# ESP8266_WS.net
KiCad netlist of a schematic drawn in EasyEDA
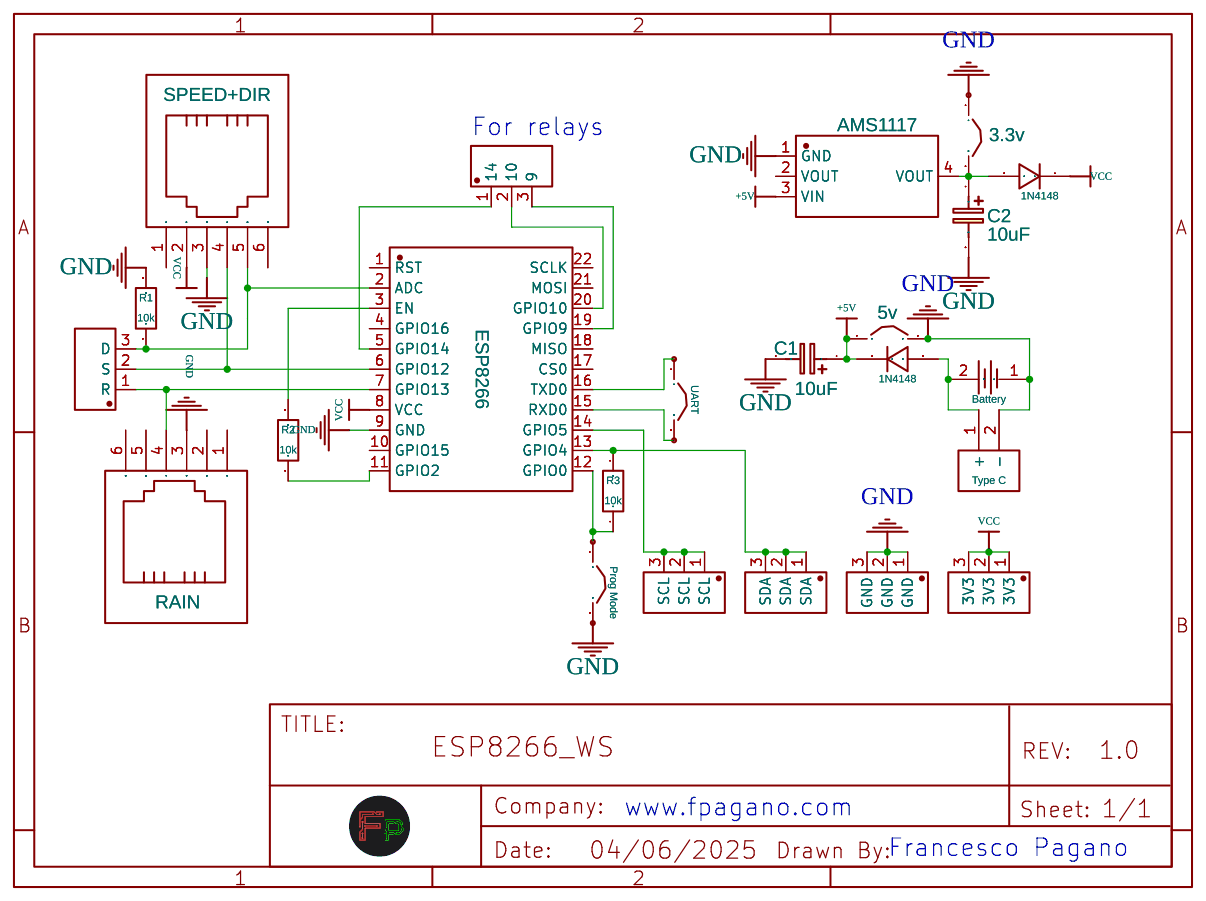
[diagram p0: schematic sheet]

(export (version "E")
  (design (tool "Eeschema 10.0.6"))
  (components
    (comp (ref "3V3") (value "3V3") (libsource (lib "") (part "HEADER FEMALE 2.54 1X3_5")))
    (comp (ref "AMS1117")
      (value "AMS1117")
      (fields (field (name "Manufacturer Part") "AMS1117-3.3") (field (name "Manufacturer") "AMS"))
      (libsource (lib "") (part "AMS1117-3.3"))
    )
    (comp (ref "BATTERY")
      (value "Battery")
      (fields
        (field (name "Manufacturer Part") "BH-18650-B6AA002")
        (field (name "Manufacturer") "MYOUNG(美阳)")
      )
      (libsource (lib "") (part "BH-18650-B6AA002"))
    )
    (comp (ref "C1") (value "10uF") (libsource (lib "") (part "CE_TH_D4.0×F1.5_EU_1")))
    (comp (ref "C2") (value "10uF") (libsource (lib "") (part "CE_TH_D4.0×F1.5_EU")))
    (comp (ref "D1")
      (value "1N4148")
      (fields (field (name "Manufacturer") "STMicroelectronics"))
      (libsource (lib "") (part "1N4148_1"))
    )
    (comp (ref "D2")
      (value "1N4148")
      (fields (field (name "Manufacturer") "STMicroelectronics"))
      (libsource (lib "") (part "1N4148"))
    )
    (comp (ref "ESP8266") (value "ESP8266") (libsource (lib "") (part "ESP8266")))
    (comp (ref "GND") (value "GND") (libsource (lib "") (part "HEADER FEMALE 2.54 1X3_3")))
    (comp (ref "GPIO") (value "GPIO") (libsource (lib "") (part "HEADER FEMALE 2.54 1X3_4")))
    (comp (ref "J-3V3")
      (value "3.3v")
      (fields (field (name "Manufacturer Part") "NONE"))
      (libsource (lib "") (part "JUMPERTHRUHOLE_2"))
    )
    (comp (ref "J-5V")
      (value "5v")
      (fields (field (name "Manufacturer Part") "NONE"))
      (libsource (lib "") (part "JUMPERTHRUHOLE"))
    )
    (comp (ref "OUT") (value "OUT") (libsource (lib "") (part "HEADER FEMALE 2.54 1X3_2")))
    (comp (ref "PROG-MODE")
      (value "Prog Mode")
      (fields (field (name "Manufacturer Part") "NONE"))
      (libsource (lib "") (part "JUMPERTHRUHOLE_3"))
    )
    (comp (ref "R1") (value "10k") (libsource (lib "") (part "R_AXIAL-0.3_EU")))
    (comp (ref "R2") (value "10k") (libsource (lib "") (part "R_AXIAL-0.3_EU")))
    (comp (ref "R3") (value "10k") (libsource (lib "") (part "R_AXIAL-0.3_EU")))
    (comp (ref "RAIN")
      (value "RAIN")
      (fields (field (name "Manufacturer Part") "331-6421") (field (name "Manufacturer") "RS PRO"))
      (libsource (lib "") (part "ARUN--RJ11-6P6C"))
    )
    (comp (ref "SCL") (value "SCL") (libsource (lib "") (part "HEADER FEMALE 2.54 1X3_1")))
    (comp (ref "SDA") (value "SDA") (libsource (lib "") (part "HEADER FEMALE 2.54 1X3")))
    (comp (ref "SPEED-DIRECTION")
      (value "SPEED+DIR")
      (fields (field (name "Manufacturer Part") "331-6421") (field (name "Manufacturer") "RS PRO"))
      (libsource (lib "") (part "ARUN--RJ11-6P6C_1"))
    )
    (comp (ref "TYPEC") (value "Type C") (libsource (lib "") (part "usb type C 2 pin")))
    (comp (ref "UART")
      (value "UART")
      (fields (field (name "Manufacturer Part") "NONE"))
      (libsource (lib "") (part "JUMPERTHRUHOLE_1"))
    )
  )
  (nets
    (net (code "1") (name "+5V") (class "Default")
      (node (ref "AMS1117") (pin "3") (pinfunction "VIN_3") (pintype "unspecified"))
      (node (ref "C1") (pin "1") (pinfunction "1_1") (pintype "unspecified"))
      (node (ref "D1") (pin "1") (pinfunction "1_1") (pintype "unspecified"))
      (node (ref "J-5V") (pin "1") (pinfunction "1_1") (pintype "unspecified"))
    )
    (net (code "2") (name "GND") (class "Default")
      (node (ref "AMS1117") (pin "1") (pinfunction "GND_1") (pintype "unspecified"))
      (node (ref "BATTERY") (pin "1") (pinfunction "1_1") (pintype "input"))
      (node (ref "C1") (pin "2") (pinfunction "2_2") (pintype "unspecified"))
      (node (ref "C2") (pin "2") (pinfunction "2_2") (pintype "unspecified"))
      (node (ref "ESP8266") (pin "9") (pinfunction "GND_9") (pintype "unspecified"))
      (node (ref "GND") (pin "1") (pinfunction "GND_1") (pintype "unspecified"))
      (node (ref "GND") (pin "2") (pinfunction "GND_2") (pintype "unspecified"))
      (node (ref "GND") (pin "3") (pinfunction "GND_3") (pintype "unspecified"))
      (node (ref "J-3V3") (pin "1") (pinfunction "1_1") (pintype "unspecified"))
      (node (ref "J-5V") (pin "2") (pinfunction "2_2") (pintype "unspecified"))
      (node (ref "PROG-MODE") (pin "2") (pinfunction "2_2") (pintype "unspecified"))
      (node (ref "R1") (pin "2") (pinfunction "2_2") (pintype "unspecified"))
      (node (ref "RAIN") (pin "3") (pinfunction "3_3") (pintype "unspecified"))
      (node (ref "SPEED-DIRECTION") (pin "3") (pinfunction "3_3") (pintype "unspecified"))
      (node (ref "TYPEC") (pin "2") (pinfunction "-_2") (pintype "unspecified"))
    )
    (net (code "3") (name "Net-(AMS1117-VOUT-Pad4)") (class "Default")
      (node (ref "AMS1117") (pin "4") (pinfunction "VOUT_4") (pintype "unspecified"))
      (node (ref "C2") (pin "1") (pinfunction "1_1") (pintype "unspecified"))
      (node (ref "D2") (pin "2") (pinfunction "2_2") (pintype "unspecified"))
      (node (ref "J-3V3") (pin "2") (pinfunction "2_2") (pintype "unspecified"))
    )
    (net (code "4") (name "Net-(ESP8266-ADC)") (class "Default")
      (node (ref "ESP8266") (pin "2") (pinfunction "ADC_2") (pintype "unspecified"))
      (node (ref "OUT") (pin "3") (pinfunction "D_3") (pintype "unspecified"))
      (node (ref "R1") (pin "1") (pinfunction "1_1") (pintype "unspecified"))
      (node (ref "SPEED-DIRECTION") (pin "5") (pinfunction "5_5") (pintype "unspecified"))
    )
    (net (code "5") (name "Net-(ESP8266-EN)") (class "Default")
      (node (ref "ESP8266") (pin "3") (pinfunction "EN_3") (pintype "unspecified"))
      (node (ref "R2") (pin "2") (pinfunction "2_2") (pintype "unspecified"))
    )
    (net (code "6") (name "Net-(ESP8266-GPIO0)") (class "Default")
      (node (ref "ESP8266") (pin "12") (pinfunction "GPIO0_12") (pintype "unspecified"))
      (node (ref "PROG-MODE") (pin "1") (pinfunction "1_1") (pintype "unspecified"))
      (node (ref "R3") (pin "1") (pinfunction "1_1") (pintype "unspecified"))
    )
    (net (code "7") (name "Net-(ESP8266-GPIO2)") (class "Default")
      (node (ref "ESP8266") (pin "11") (pinfunction "GPIO2_11") (pintype "unspecified"))
      (node (ref "R2") (pin "1") (pinfunction "1_1") (pintype "unspecified"))
    )
    (net (code "8") (name "Net-(ESP8266-GPIO4)") (class "Default")
      (node (ref "ESP8266") (pin "13") (pinfunction "GPIO4_13") (pintype "unspecified"))
      (node (ref "R3") (pin "2") (pinfunction "2_2") (pintype "unspecified"))
      (node (ref "SDA") (pin "1") (pinfunction "SDA_1") (pintype "unspecified"))
      (node (ref "SDA") (pin "2") (pinfunction "SDA_2") (pintype "unspecified"))
      (node (ref "SDA") (pin "3") (pinfunction "SDA_3") (pintype "unspecified"))
    )
    (net (code "9") (name "Net-(ESP8266-GPIO5)") (class "Default")
      (node (ref "ESP8266") (pin "14") (pinfunction "GPIO5_14") (pintype "unspecified"))
      (node (ref "SCL") (pin "1") (pinfunction "SCL_1") (pintype "unspecified"))
      (node (ref "SCL") (pin "2") (pinfunction "SCL_2") (pintype "unspecified"))
      (node (ref "SCL") (pin "3") (pinfunction "SCL_3") (pintype "unspecified"))
    )
    (net (code "10") (name "Net-(ESP8266-GPIO9)") (class "Default")
      (node (ref "ESP8266") (pin "19") (pinfunction "GPIO9_19") (pintype "unspecified"))
      (node (ref "GPIO") (pin "3") (pinfunction "9_3") (pintype "unspecified"))
    )
    (net (code "11") (name "Net-(ESP8266-GPIO10)") (class "Default")
      (node (ref "ESP8266") (pin "20") (pinfunction "GPIO10_20") (pintype "unspecified"))
      (node (ref "GPIO") (pin "2") (pinfunction "10_2") (pintype "unspecified"))
    )
    (net (code "12") (name "Net-(ESP8266-GPIO12)") (class "Default")
      (node (ref "ESP8266") (pin "6") (pinfunction "GPIO12_6") (pintype "unspecified"))
      (node (ref "OUT") (pin "2") (pinfunction "S_2") (pintype "unspecified"))
      (node (ref "SPEED-DIRECTION") (pin "4") (pinfunction "4_4") (pintype "unspecified"))
    )
    (net (code "13") (name "Net-(ESP8266-GPIO13)") (class "Default")
      (node (ref "ESP8266") (pin "7") (pinfunction "GPIO13_7") (pintype "unspecified"))
      (node (ref "OUT") (pin "1") (pinfunction "R_1") (pintype "unspecified"))
      (node (ref "RAIN") (pin "4") (pinfunction "4_4") (pintype "unspecified"))
    )
    (net (code "14") (name "Net-(ESP8266-GPIO14)") (class "Default")
      (node (ref "ESP8266") (pin "5") (pinfunction "GPIO14_5") (pintype "unspecified"))
      (node (ref "GPIO") (pin "1") (pinfunction "14_1") (pintype "unspecified"))
    )
    (net (code "15") (name "Net-(ESP8266-RXD0)") (class "Default")
      (node (ref "ESP8266") (pin "15") (pinfunction "RXD0_15") (pintype "unspecified"))
      (node (ref "UART") (pin "2") (pinfunction "2_2") (pintype "unspecified"))
    )
    (net (code "16") (name "Net-(ESP8266-TXD0)") (class "Default")
      (node (ref "ESP8266") (pin "16") (pinfunction "TXD0_16") (pintype "unspecified"))
      (node (ref "UART") (pin "1") (pinfunction "1_1") (pintype "unspecified"))
    )
    (net (code "17") (name "Net-(TYPEC-+)") (class "Default")
      (node (ref "BATTERY") (pin "2") (pinfunction "2_2") (pintype "input"))
      (node (ref "D1") (pin "2") (pinfunction "2_2") (pintype "unspecified"))
      (node (ref "TYPEC") (pin "1") (pinfunction "+_1") (pintype "unspecified"))
    )
    (net (code "18") (name "VCC") (class "Default")
      (node (ref "3V3") (pin "1") (pinfunction "3V3_1") (pintype "unspecified"))
      (node (ref "3V3") (pin "2") (pinfunction "3V3_2") (pintype "unspecified"))
      (node (ref "3V3") (pin "3") (pinfunction "3V3_3") (pintype "unspecified"))
      (node (ref "D2") (pin "1") (pinfunction "1_1") (pintype "unspecified"))
      (node (ref "ESP8266") (pin "8") (pinfunction "VCC_8") (pintype "unspecified"))
      (node (ref "SPEED-DIRECTION") (pin "2") (pinfunction "2_2") (pintype "unspecified"))
    )
    (net (code "19") (name "unconnected-(AMS1117-VOUT-Pad2)") (class "Default")
      (node (ref "AMS1117") (pin "2") (pinfunction "VOUT_2") (pintype "unspecified"))
    )
    (net (code "20") (name "unconnected-(ESP8266-CS0-Pad17)") (class "Default")
      (node (ref "ESP8266") (pin "17") (pinfunction "CS0_17") (pintype "unspecified"))
    )
    (net (code "21") (name "unconnected-(ESP8266-GPIO15-Pad10)") (class "Default")
      (node (ref "ESP8266") (pin "10") (pinfunction "GPIO15_10") (pintype "unspecified"))
    )
    (net (code "22") (name "unconnected-(ESP8266-GPIO16-Pad4)") (class "Default")
      (node (ref "ESP8266") (pin "4") (pinfunction "GPIO16_4") (pintype "unspecified"))
    )
    (net (code "23") (name "unconnected-(ESP8266-MISO-Pad18)") (class "Default")
      (node (ref "ESP8266") (pin "18") (pinfunction "MISO_18") (pintype "unspecified"))
    )
    (net (code "24") (name "unconnected-(ESP8266-MOSI-Pad21)") (class "Default")
      (node (ref "ESP8266") (pin "21") (pinfunction "MOSI_21") (pintype "unspecified"))
    )
    (net (code "25") (name "unconnected-(ESP8266-RST-Pad1)") (class "Default")
      (node (ref "ESP8266") (pin "1") (pinfunction "RST_1") (pintype "unspecified"))
    )
    (net (code "26") (name "unconnected-(ESP8266-SCLK-Pad22)") (class "Default")
      (node (ref "ESP8266") (pin "22") (pinfunction "SCLK_22") (pintype "unspecified"))
    )
    (net (code "27") (name "unconnected-(RAIN-Pad1)") (class "Default")
      (node (ref "RAIN") (pin "1") (pinfunction "1_1") (pintype "unspecified"))
    )
    (net (code "28") (name "unconnected-(RAIN-Pad2)") (class "Default")
      (node (ref "RAIN") (pin "2") (pinfunction "2_2") (pintype "unspecified"))
    )
    (net (code "29") (name "unconnected-(RAIN-Pad5)") (class "Default")
      (node (ref "RAIN") (pin "5") (pinfunction "5_5") (pintype "unspecified"))
    )
    (net (code "30") (name "unconnected-(RAIN-Pad6)") (class "Default")
      (node (ref "RAIN") (pin "6") (pinfunction "6_6") (pintype "unspecified"))
    )
    (net (code "31") (name "unconnected-(SPEED-DIRECTION-Pad1)") (class "Default")
      (node (ref "SPEED-DIRECTION") (pin "1") (pinfunction "1_1") (pintype "unspecified"))
    )
    (net (code "32") (name "unconnected-(SPEED-DIRECTION-Pad6)") (class "Default")
      (node (ref "SPEED-DIRECTION") (pin "6") (pinfunction "6_6") (pintype "unspecified"))
    )
  )
)
